# CurrentSense.net
KiCad netlist of a schematic drawn in Altium Designer
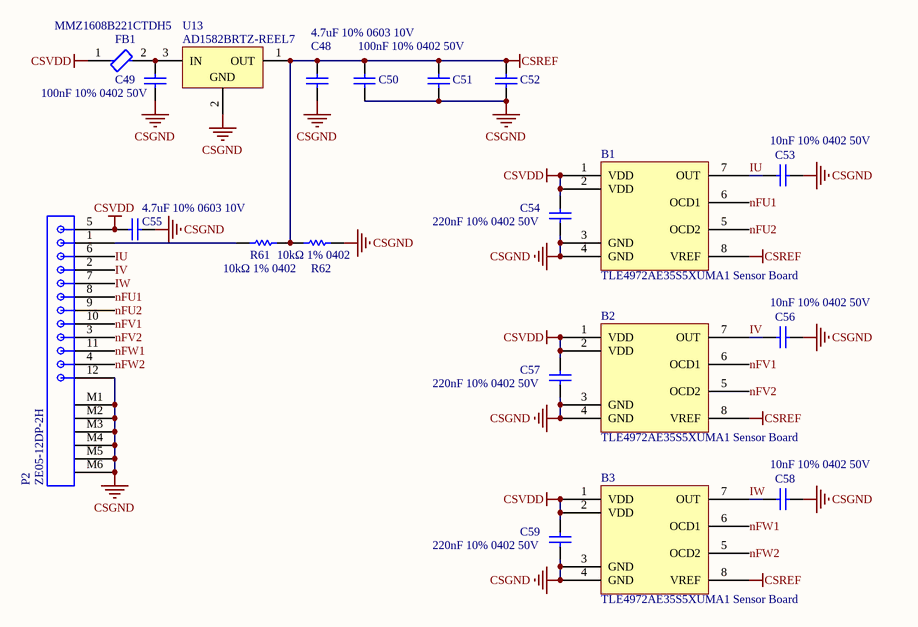
[diagram p0: CurrentSense.SchDoc]

(export (version "E")
  (design (tool "Eeschema 10.0.6"))
  (components
    (comp (ref "B1")
      (value "TLE4972AE35S5XUMA1 Sensor Board")
      (footprint "TLE4972AE35S5XUMA1 Sensor Board-Footprint-1")
      (libsource (lib "Saule S.A") (part "TLE4972AE35S5XUMA1 Sensor Board-Symbol-1"))
    )
    (comp (ref "B2")
      (value "TLE4972AE35S5XUMA1 Sensor Board")
      (footprint "TLE4972AE35S5XUMA1 Sensor Board-Footprint-1")
      (libsource (lib "Saule S.A") (part "TLE4972AE35S5XUMA1 Sensor Board-Symbol-1"))
    )
    (comp (ref "B3")
      (value "TLE4972AE35S5XUMA1 Sensor Board")
      (footprint "TLE4972AE35S5XUMA1 Sensor Board-Footprint-1")
      (libsource (lib "Saule S.A") (part "TLE4972AE35S5XUMA1 Sensor Board-Symbol-1"))
    )
    (comp (ref "C48")
      (value "4.7uF 10% 0603 10V")
      (footprint "0603L")
      (fields (field (name "TOLERANCE") "10"))
      (libsource (lib "MiscPassives") (part "C0603"))
    )
    (comp (ref "C49")
      (value "100nF 10% 0402 50V")
      (footprint "0402N")
      (fields (field (name "TOLERANCE") "10") (field (name "VOLTAGE") "50"))
      (libsource (lib "MiscPassives") (part "C0402"))
    )
    (comp (ref "C50")
      (value "100nF 10% 0402 50V")
      (footprint "0402N")
      (fields (field (name "TOLERANCE") "10") (field (name "VOLTAGE") "50"))
      (libsource (lib "MiscPassives") (part "C0402"))
    )
    (comp (ref "C51")
      (value "100nF 10% 0402 50V")
      (footprint "0402N")
      (fields (field (name "TOLERANCE") "10") (field (name "VOLTAGE") "50"))
      (libsource (lib "MiscPassives") (part "C0402"))
    )
    (comp (ref "C52")
      (value "100nF 10% 0402 50V")
      (footprint "0402N")
      (fields (field (name "TOLERANCE") "10") (field (name "VOLTAGE") "50"))
      (libsource (lib "MiscPassives") (part "C0402"))
    )
    (comp (ref "C53")
      (value "10nF 10% 0402 50V")
      (footprint "0402N")
      (fields (field (name "TOLERANCE") "10") (field (name "VOLTAGE") "50"))
      (libsource (lib "MiscPassives") (part "C0402"))
    )
    (comp (ref "C54")
      (value "220nF 10% 0402 50V")
      (footprint "0402N")
      (fields (field (name "TOLERANCE") "10") (field (name "VOLTAGE") "50"))
      (libsource (lib "MiscPassives") (part "C0402"))
    )
    (comp (ref "C55")
      (value "4.7uF 10% 0603 10V")
      (footprint "0603L")
      (fields (field (name "TOLERANCE") "10"))
      (libsource (lib "MiscPassives") (part "C0603"))
    )
    (comp (ref "C56")
      (value "10nF 10% 0402 50V")
      (footprint "0402N")
      (fields (field (name "TOLERANCE") "10") (field (name "VOLTAGE") "50"))
      (libsource (lib "MiscPassives") (part "C0402"))
    )
    (comp (ref "C57")
      (value "220nF 10% 0402 50V")
      (footprint "0402N")
      (fields (field (name "TOLERANCE") "10") (field (name "VOLTAGE") "50"))
      (libsource (lib "MiscPassives") (part "C0402"))
    )
    (comp (ref "C58")
      (value "10nF 10% 0402 50V")
      (footprint "0402N")
      (fields (field (name "TOLERANCE") "10") (field (name "VOLTAGE") "50"))
      (libsource (lib "MiscPassives") (part "C0402"))
    )
    (comp (ref "C59")
      (value "220nF 10% 0402 50V")
      (footprint "0402N")
      (fields (field (name "TOLERANCE") "10") (field (name "VOLTAGE") "50"))
      (libsource (lib "MiscPassives") (part "C0402"))
    )
    (comp (ref "FB1")
      (value "MMZ1608B221CTDH5")
      (footprint "FP-MMZ1608-0_6-MFG")
      (description "Signal Line Ferrite Bead 220 Ω 100MHz 500mA DCR 250mΩ AEC-Q200 SMD 0603")
      (fields (field (name "TOLERANCE") "25%"))
      (libsource (lib "Altium Content Vault") (part "5f30dd21d616792df468990f7003faa"))
    )
    (comp (ref "P2")
      (value "ZE05-12DP-2H")
      (footprint "ZE05-12DP-2H-Footprint-1")
      (libsource (lib "Saule S.A") (part "ZE05-12DP-2H-Symbol-1"))
    )
    (comp (ref "R61")
      (value "10kΩ 1% 0402")
      (footprint "0402N")
      (fields (field (name "TOLERANCE") "1"))
      (libsource (lib "MiscPassives") (part "R0402"))
    )
    (comp (ref "R62")
      (value "10kΩ 1% 0402")
      (footprint "0402N")
      (fields (field (name "TOLERANCE") "1"))
      (libsource (lib "MiscPassives") (part "R0402"))
    )
    (comp (ref "U13")
      (value "AD1582BRTZ-REEL7")
      (footprint "ADI-RT-3_M")
      (fields (field (name "MANUFACTURER") "Analog Devices"))
      (libsource (lib "Altium Content Vault") (part "ADI-AD158X-RT-3"))
    )
  )
  (nets
    (net (code "1") (name "/IU") (class "Default")
      (node (ref "B1") (pin "7") (pinfunction "OUT_7") (pintype "passive"))
      (node (ref "C53") (pin "2") (pinfunction "2_2") (pintype "passive"))
      (node (ref "P2") (pin "6") (pinfunction "6_6") (pintype "passive"))
    )
    (net (code "2") (name "/IV") (class "Default")
      (node (ref "B2") (pin "7") (pinfunction "OUT_7") (pintype "passive"))
      (node (ref "C56") (pin "2") (pinfunction "2_2") (pintype "passive"))
      (node (ref "P2") (pin "2") (pinfunction "2_2") (pintype "passive"))
    )
    (net (code "3") (name "/IW") (class "Default")
      (node (ref "B3") (pin "7") (pinfunction "OUT_7") (pintype "passive"))
      (node (ref "C58") (pin "2") (pinfunction "2_2") (pintype "passive"))
      (node (ref "P2") (pin "7") (pinfunction "7_7") (pintype "passive"))
    )
    (net (code "4") (name "/nFU1") (class "Default")
      (node (ref "B1") (pin "6") (pinfunction "OCD1_6") (pintype "passive"))
      (node (ref "P2") (pin "8") (pinfunction "8_8") (pintype "passive"))
    )
    (net (code "5") (name "/nFU2") (class "Default")
      (node (ref "B1") (pin "5") (pinfunction "OCD2_5") (pintype "passive"))
      (node (ref "P2") (pin "9") (pinfunction "9_9") (pintype "passive"))
    )
    (net (code "6") (name "/nFV1") (class "Default")
      (node (ref "B2") (pin "6") (pinfunction "OCD1_6") (pintype "passive"))
      (node (ref "P2") (pin "10") (pinfunction "10_10") (pintype "passive"))
    )
    (net (code "7") (name "/nFV2") (class "Default")
      (node (ref "B2") (pin "5") (pinfunction "OCD2_5") (pintype "passive"))
      (node (ref "P2") (pin "3") (pinfunction "3_3") (pintype "passive"))
    )
    (net (code "8") (name "/nFW1") (class "Default")
      (node (ref "B3") (pin "6") (pinfunction "OCD1_6") (pintype "passive"))
      (node (ref "P2") (pin "11") (pinfunction "11_11") (pintype "passive"))
    )
    (net (code "9") (name "/nFW2") (class "Default")
      (node (ref "B3") (pin "5") (pinfunction "OCD2_5") (pintype "passive"))
      (node (ref "P2") (pin "4") (pinfunction "4_4") (pintype "passive"))
    )
    (net (code "10") (name "CSGND") (class "Default")
      (node (ref "B1") (pin "3") (pinfunction "GND_3") (pintype "passive"))
      (node (ref "B1") (pin "4") (pinfunction "GND_4") (pintype "passive"))
      (node (ref "B2") (pin "3") (pinfunction "GND_3") (pintype "passive"))
      (node (ref "B2") (pin "4") (pinfunction "GND_4") (pintype "passive"))
      (node (ref "B3") (pin "3") (pinfunction "GND_3") (pintype "passive"))
      (node (ref "B3") (pin "4") (pinfunction "GND_4") (pintype "passive"))
      (node (ref "C48") (pin "1") (pinfunction "1_1") (pintype "passive"))
      (node (ref "C49") (pin "1") (pinfunction "1_1") (pintype "passive"))
      (node (ref "C50") (pin "1") (pinfunction "1_1") (pintype "passive"))
      (node (ref "C51") (pin "1") (pinfunction "1_1") (pintype "passive"))
      (node (ref "C52") (pin "1") (pinfunction "1_1") (pintype "passive"))
      (node (ref "C53") (pin "1") (pinfunction "1_1") (pintype "passive"))
      (node (ref "C54") (pin "1") (pinfunction "1_1") (pintype "passive"))
      (node (ref "C55") (pin "1") (pinfunction "1_1") (pintype "passive"))
      (node (ref "C56") (pin "1") (pinfunction "1_1") (pintype "passive"))
      (node (ref "C57") (pin "1") (pinfunction "1_1") (pintype "passive"))
      (node (ref "C58") (pin "1") (pinfunction "1_1") (pintype "passive"))
      (node (ref "C59") (pin "1") (pinfunction "1_1") (pintype "passive"))
      (node (ref "P2") (pin "12") (pinfunction "12_12") (pintype "passive"))
      (node (ref "P2") (pin "M1") (pinfunction "M1_M1") (pintype "passive"))
      (node (ref "P2") (pin "M2") (pinfunction "M2_M2") (pintype "passive"))
      (node (ref "P2") (pin "M3") (pinfunction "M3_M3") (pintype "passive"))
      (node (ref "P2") (pin "M4") (pinfunction "M4_M4") (pintype "passive"))
      (node (ref "P2") (pin "M5") (pinfunction "M5_M5") (pintype "passive"))
      (node (ref "P2") (pin "M6") (pinfunction "M6_M6") (pintype "passive"))
      (node (ref "R62") (pin "2") (pinfunction "2_2") (pintype "passive"))
      (node (ref "U13") (pin "2") (pinfunction "GND_2") (pintype "power_in"))
    )
    (net (code "11") (name "CSREF") (class "Default")
      (node (ref "B1") (pin "8") (pinfunction "VREF_8") (pintype "passive"))
      (node (ref "B2") (pin "8") (pinfunction "VREF_8") (pintype "passive"))
      (node (ref "B3") (pin "8") (pinfunction "VREF_8") (pintype "passive"))
      (node (ref "C48") (pin "2") (pinfunction "2_2") (pintype "passive"))
      (node (ref "C50") (pin "2") (pinfunction "2_2") (pintype "passive"))
      (node (ref "C51") (pin "2") (pinfunction "2_2") (pintype "passive"))
      (node (ref "C52") (pin "2") (pinfunction "2_2") (pintype "passive"))
      (node (ref "R61") (pin "2") (pinfunction "2_2") (pintype "passive"))
      (node (ref "R62") (pin "1") (pinfunction "1_1") (pintype "passive"))
      (node (ref "U13") (pin "1") (pinfunction "OUT_1") (pintype "power_in"))
    )
    (net (code "12") (name "CSVDD") (class "Default")
      (node (ref "B1") (pin "1") (pinfunction "VDD_1") (pintype "passive"))
      (node (ref "B1") (pin "2") (pinfunction "VDD_2") (pintype "passive"))
      (node (ref "B2") (pin "1") (pinfunction "VDD_1") (pintype "passive"))
      (node (ref "B2") (pin "2") (pinfunction "VDD_2") (pintype "passive"))
      (node (ref "B3") (pin "1") (pinfunction "VDD_1") (pintype "passive"))
      (node (ref "B3") (pin "2") (pinfunction "VDD_2") (pintype "passive"))
      (node (ref "C54") (pin "2") (pinfunction "2_2") (pintype "passive"))
      (node (ref "C55") (pin "2") (pinfunction "2_2") (pintype "passive"))
      (node (ref "C57") (pin "2") (pinfunction "2_2") (pintype "passive"))
      (node (ref "C59") (pin "2") (pinfunction "2_2") (pintype "passive"))
      (node (ref "FB1") (pin "1") (pinfunction "1_1") (pintype "passive"))
      (node (ref "P2") (pin "5") (pinfunction "5_5") (pintype "passive"))
    )
    (net (code "13") (name "Net-(P2-Pad1)") (class "Default")
      (node (ref "P2") (pin "1") (pinfunction "1_1") (pintype "passive"))
      (node (ref "R61") (pin "1") (pinfunction "1_1") (pintype "passive"))
    )
    (net (code "14") (name "Net-(U13-IN)") (class "Default")
      (node (ref "C49") (pin "2") (pinfunction "2_2") (pintype "passive"))
      (node (ref "FB1") (pin "2") (pinfunction "2_2") (pintype "passive"))
      (node (ref "U13") (pin "3") (pinfunction "IN_3") (pintype "power_in"))
    )
  )
)
